# design.net
KiCad netlist of a schematic drawn in Altium Designer
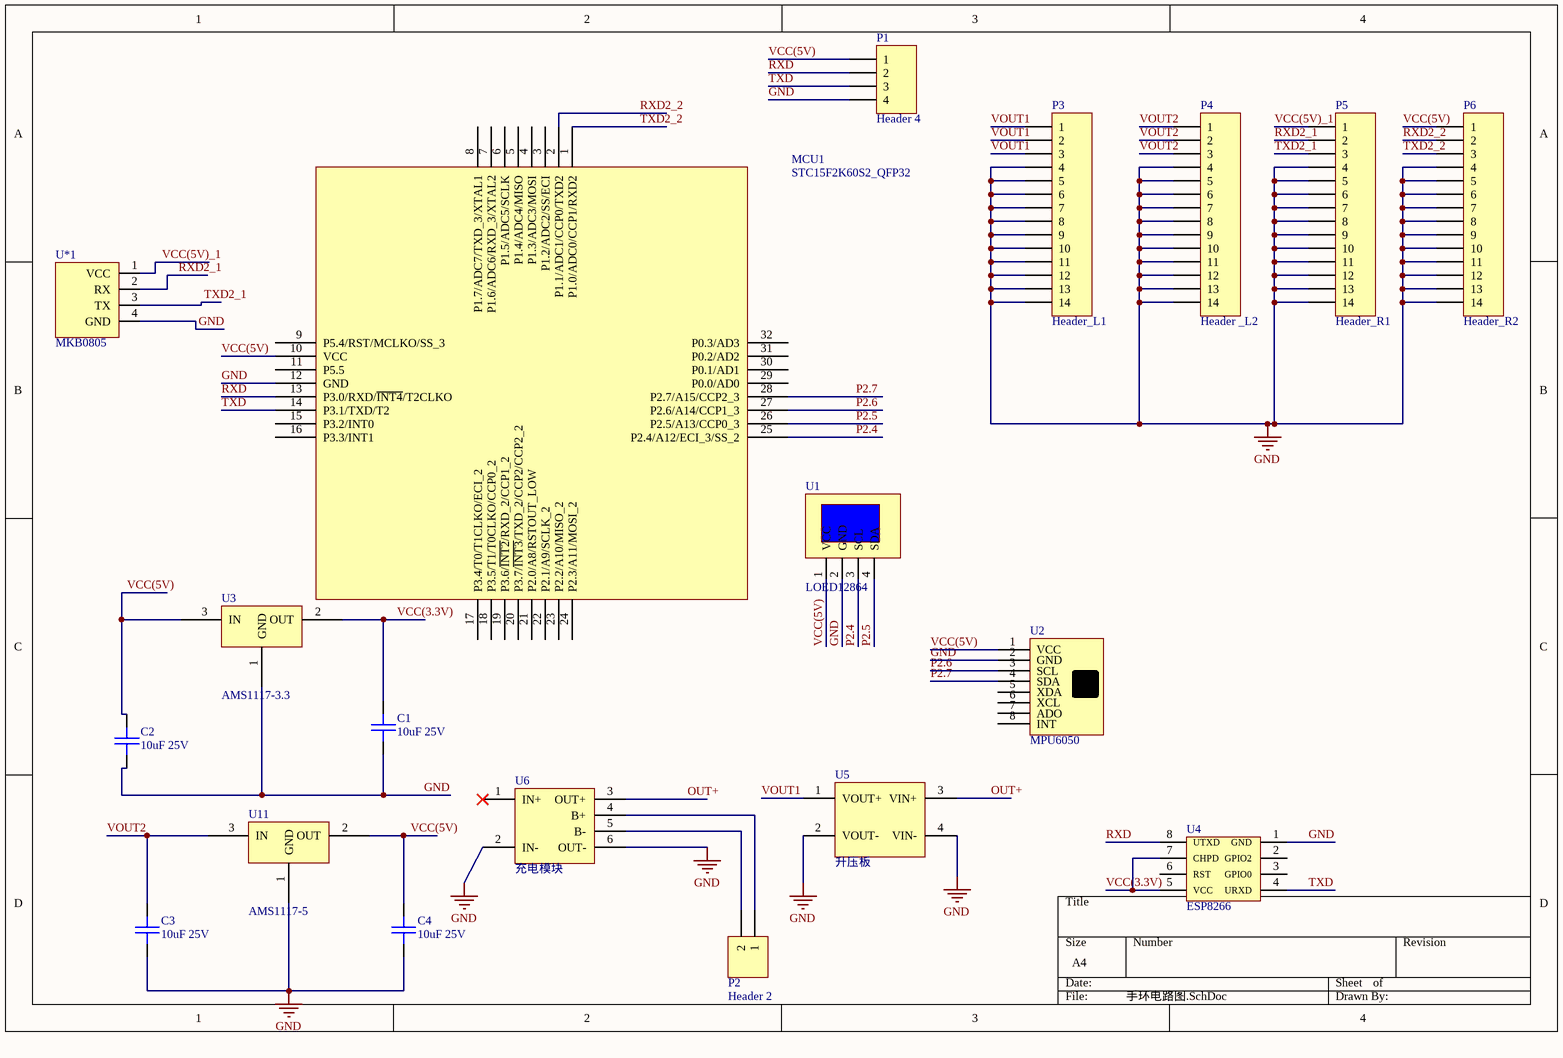
[diagram p0: 手环电路图.SchDoc]

(export (version "E")
  (design (tool "Eeschema 10.0.6"))
  (components
    (comp (ref "C1")
      (value "10uF 25V")
      (footprint "SMT_C_0805")
      (description "Surface mount capacitor 0805")
      (libsource (lib "NODEMCU_DEVKIT_V1.0") (part "SMT_C_0805"))
    )
    (comp (ref "C2")
      (value "10uF 25V")
      (footprint "SMT_C_0805")
      (description "Surface mount capacitor 0805")
      (libsource (lib "NODEMCU_DEVKIT_V1.0") (part "SMT_C_0805"))
    )
    (comp (ref "C3")
      (value "10uF 25V")
      (footprint "SMT_C_0805")
      (description "Surface mount capacitor 0805")
      (libsource (lib "NODEMCU_DEVKIT_V1.0") (part "SMT_C_0805"))
    )
    (comp (ref "C4")
      (value "10uF 25V")
      (footprint "SMT_C_0805")
      (description "Surface mount capacitor 0805")
      (libsource (lib "NODEMCU_DEVKIT_V1.0") (part "SMT_C_0805"))
    )
    (comp (ref "MCU1")
      (value "STC15F2K60S2_QFP32")
      (footprint "LQFP32")
      (libsource (lib "stcmcu_altium_lib") (part "STC15F2K60S2_QFP32"))
    )
    (comp (ref "P1")
      (value "Header 4")
      (footprint "HDR1X4")
      (description "Header, 4-Pin")
      (fields (field (name "PUBLISHER") "Altium Limited"))
      (libsource (lib "Miscellaneous Connectors") (part "Header 4"))
    )
    (comp (ref "P2")
      (value "Header 2")
      (footprint "HDR1X2")
      (description "Header, 2-Pin")
      (fields (field (name "PUBLISHER") "Altium Limited"))
      (libsource (lib "Miscellaneous Connectors") (part "Header 2"))
    )
    (comp (ref "P3")
      (value "Header_L1")
      (footprint "HDR1X14")
      (description "Header, 14-Pin")
      (fields (field (name "PUBLISHER") "Altium Limited"))
      (libsource (lib "Miscellaneous Connectors") (part "Header 14"))
    )
    (comp (ref "P4")
      (value "Header _L2")
      (footprint "HDR1X14")
      (description "Header, 14-Pin")
      (fields (field (name "PUBLISHER") "Altium Limited"))
      (libsource (lib "Miscellaneous Connectors") (part "Header 14"))
    )
    (comp (ref "P5")
      (value "Header_R1")
      (footprint "HDR1X14")
      (description "Header, 14-Pin")
      (fields (field (name "PUBLISHER") "Altium Limited"))
      (libsource (lib "Miscellaneous Connectors") (part "Header 14"))
    )
    (comp (ref "P6")
      (value "Header_R2")
      (footprint "HDR1X14")
      (description "Header, 14-Pin")
      (fields (field (name "PUBLISHER") "Altium Limited"))
      (libsource (lib "Miscellaneous Connectors") (part "Header 14"))
    )
    (comp (ref "U*1") (value "MKB0805") (footprint "MKB0805") (libsource (lib "oldman") (part "MKB0805")))
    (comp (ref "U1")
      (value "LOED12864")
      (footprint "OLED12864")
      (libsource (lib "oldman") (part "LOED12864"))
    )
    (comp (ref "U2") (value "MPU6050") (footprint "MPU6050") (libsource (lib "oldman") (part "MPU6050")))
    (comp (ref "U3") (value "AMS1117-3.3") (footprint "AMS1117") (libsource (lib "NFC") (part "AMS1117-3.3")))
    (comp (ref "U4") (value "ESP8266") (footprint "ESP8266") (libsource (lib "oldman") (part "ESP8266")))
    (comp (ref "U5") (value "升压板") (footprint "MT3608") (libsource (lib "oldman") (part "MT3608")))
    (comp (ref "U6") (value "充电模块") (footprint "HW373") (libsource (lib "oldman") (part "HW373")))
    (comp (ref "U11") (value "AMS1117-5") (footprint "AMS1117") (libsource (lib "NFC") (part "AMS1117-3.3")))
  )
  (nets
    (net (code "1") (name "/OUT+") (class "Default")
      (node (ref "U5") (pin "3") (pinfunction "VIN+_3") (pintype "passive"))
      (node (ref "U6") (pin "3") (pinfunction "OUT+_3") (pintype "passive"))
    )
    (net (code "2") (name "/P2.4") (class "Default")
      (node (ref "MCU1") (pin "25") (pinfunction "P2.4/A12/ECI_3/SS_2_25") (pintype "passive"))
      (node (ref "U1") (pin "3") (pinfunction "SCL_3") (pintype "passive"))
    )
    (net (code "3") (name "/P2.5") (class "Default")
      (node (ref "MCU1") (pin "26") (pinfunction "P2.5/A13/CCP0_3_26") (pintype "passive"))
      (node (ref "U1") (pin "4") (pinfunction "SDA_4") (pintype "passive"))
    )
    (net (code "4") (name "/P2.6") (class "Default")
      (node (ref "MCU1") (pin "27") (pinfunction "P2.6/A14/CCP1_3_27") (pintype "passive"))
      (node (ref "U2") (pin "3") (pinfunction "SCL_3") (pintype "passive"))
    )
    (net (code "5") (name "/P2.7") (class "Default")
      (node (ref "MCU1") (pin "28") (pinfunction "P2.7/A15/CCP2_3_28") (pintype "passive"))
      (node (ref "U2") (pin "4") (pinfunction "SDA_4") (pintype "passive"))
    )
    (net (code "6") (name "/RXD") (class "Default")
      (node (ref "MCU1") (pin "13") (pinfunction "P3.0/RXD/~{INT4}/T2CLKO_13") (pintype "passive"))
      (node (ref "P1") (pin "2") (pinfunction "2_2") (pintype "passive"))
      (node (ref "U4") (pin "8") (pinfunction "UTXD_8") (pintype "passive"))
    )
    (net (code "7") (name "/RXD2_1") (class "Default")
      (node (ref "P5") (pin "2") (pinfunction "2_2") (pintype "passive"))
      (node (ref "U*1") (pin "2") (pinfunction "RX_2") (pintype "passive"))
    )
    (net (code "8") (name "/RXD2_2") (class "Default")
      (node (ref "MCU1") (pin "2") (pinfunction "P1.1/ADC1/CCP0/TXD2_2") (pintype "passive"))
      (node (ref "P6") (pin "2") (pinfunction "2_2") (pintype "passive"))
    )
    (net (code "9") (name "/TXD") (class "Default")
      (node (ref "MCU1") (pin "14") (pinfunction "P3.1/TXD/T2_14") (pintype "passive"))
      (node (ref "P1") (pin "3") (pinfunction "3_3") (pintype "passive"))
      (node (ref "U4") (pin "4") (pinfunction "URXD_4") (pintype "passive"))
    )
    (net (code "10") (name "/TXD2_1") (class "Default")
      (node (ref "P5") (pin "3") (pinfunction "3_3") (pintype "passive"))
      (node (ref "U*1") (pin "3") (pinfunction "TX_3") (pintype "passive"))
    )
    (net (code "11") (name "/TXD2_2") (class "Default")
      (node (ref "MCU1") (pin "1") (pinfunction "P1.0/ADC0/CCP1/RXD2_1") (pintype "passive"))
      (node (ref "P6") (pin "3") (pinfunction "3_3") (pintype "passive"))
    )
    (net (code "12") (name "/VCC(3.3V)") (class "Default")
      (node (ref "C1") (pin "1") (pinfunction "1_1") (pintype "passive"))
      (node (ref "U3") (pin "2") (pinfunction "OUT_2") (pintype "passive"))
      (node (ref "U4") (pin "5") (pinfunction "VCC_5") (pintype "power_in"))
      (node (ref "U4") (pin "7") (pinfunction "CHPD_7") (pintype "passive"))
    )
    (net (code "13") (name "/VCC(5V)") (class "Default")
      (node (ref "C2") (pin "1") (pinfunction "1_1") (pintype "passive"))
      (node (ref "C4") (pin "1") (pinfunction "1_1") (pintype "passive"))
      (node (ref "MCU1") (pin "10") (pinfunction "VCC_10") (pintype "passive"))
      (node (ref "P1") (pin "1") (pinfunction "1_1") (pintype "passive"))
      (node (ref "P6") (pin "1") (pinfunction "1_1") (pintype "passive"))
      (node (ref "U1") (pin "1") (pinfunction "VCC_1") (pintype "passive"))
      (node (ref "U11") (pin "2") (pinfunction "OUT_2") (pintype "passive"))
      (node (ref "U2") (pin "1") (pinfunction "VCC_1") (pintype "passive"))
      (node (ref "U3") (pin "3") (pinfunction "IN_3") (pintype "passive"))
    )
    (net (code "14") (name "/VCC(5V)_1") (class "Default")
      (node (ref "P5") (pin "1") (pinfunction "1_1") (pintype "passive"))
      (node (ref "U*1") (pin "1") (pinfunction "VCC_1") (pintype "passive"))
    )
    (net (code "15") (name "/VOUT1") (class "Default")
      (node (ref "P3") (pin "1") (pinfunction "1_1") (pintype "passive"))
      (node (ref "P3") (pin "2") (pinfunction "2_2") (pintype "passive"))
      (node (ref "P3") (pin "3") (pinfunction "3_3") (pintype "passive"))
      (node (ref "U5") (pin "1") (pinfunction "VOUT+_1") (pintype "passive"))
    )
    (net (code "16") (name "/VOUT2") (class "Default")
      (node (ref "C3") (pin "1") (pinfunction "1_1") (pintype "passive"))
      (node (ref "P4") (pin "1") (pinfunction "1_1") (pintype "passive"))
      (node (ref "P4") (pin "2") (pinfunction "2_2") (pintype "passive"))
      (node (ref "P4") (pin "3") (pinfunction "3_3") (pintype "passive"))
      (node (ref "U11") (pin "3") (pinfunction "IN_3") (pintype "passive"))
    )
    (net (code "17") (name "GND") (class "Default")
      (node (ref "C1") (pin "2") (pinfunction "2_2") (pintype "passive"))
      (node (ref "C2") (pin "2") (pinfunction "2_2") (pintype "passive"))
      (node (ref "C3") (pin "2") (pinfunction "2_2") (pintype "passive"))
      (node (ref "C4") (pin "2") (pinfunction "2_2") (pintype "passive"))
      (node (ref "MCU1") (pin "12") (pinfunction "GND_12") (pintype "passive"))
      (node (ref "P1") (pin "4") (pinfunction "4_4") (pintype "passive"))
      (node (ref "P3") (pin "10") (pinfunction "10_10") (pintype "passive"))
      (node (ref "P3") (pin "11") (pinfunction "11_11") (pintype "passive"))
      (node (ref "P3") (pin "12") (pinfunction "12_12") (pintype "passive"))
      (node (ref "P3") (pin "13") (pinfunction "13_13") (pintype "passive"))
      (node (ref "P3") (pin "14") (pinfunction "14_14") (pintype "passive"))
      (node (ref "P3") (pin "4") (pinfunction "4_4") (pintype "passive"))
      (node (ref "P3") (pin "5") (pinfunction "5_5") (pintype "passive"))
      (node (ref "P3") (pin "6") (pinfunction "6_6") (pintype "passive"))
      (node (ref "P3") (pin "7") (pinfunction "7_7") (pintype "passive"))
      (node (ref "P3") (pin "8") (pinfunction "8_8") (pintype "passive"))
      (node (ref "P3") (pin "9") (pinfunction "9_9") (pintype "passive"))
      (node (ref "P4") (pin "10") (pinfunction "10_10") (pintype "passive"))
      (node (ref "P4") (pin "11") (pinfunction "11_11") (pintype "passive"))
      (node (ref "P4") (pin "12") (pinfunction "12_12") (pintype "passive"))
      (node (ref "P4") (pin "13") (pinfunction "13_13") (pintype "passive"))
      (node (ref "P4") (pin "14") (pinfunction "14_14") (pintype "passive"))
      (node (ref "P4") (pin "4") (pinfunction "4_4") (pintype "passive"))
      (node (ref "P4") (pin "5") (pinfunction "5_5") (pintype "passive"))
      (node (ref "P4") (pin "6") (pinfunction "6_6") (pintype "passive"))
      (node (ref "P4") (pin "7") (pinfunction "7_7") (pintype "passive"))
      (node (ref "P4") (pin "8") (pinfunction "8_8") (pintype "passive"))
      (node (ref "P4") (pin "9") (pinfunction "9_9") (pintype "passive"))
      (node (ref "P5") (pin "10") (pinfunction "10_10") (pintype "passive"))
      (node (ref "P5") (pin "11") (pinfunction "11_11") (pintype "passive"))
      (node (ref "P5") (pin "12") (pinfunction "12_12") (pintype "passive"))
      (node (ref "P5") (pin "13") (pinfunction "13_13") (pintype "passive"))
      (node (ref "P5") (pin "14") (pinfunction "14_14") (pintype "passive"))
      (node (ref "P5") (pin "4") (pinfunction "4_4") (pintype "passive"))
      (node (ref "P5") (pin "5") (pinfunction "5_5") (pintype "passive"))
      (node (ref "P5") (pin "6") (pinfunction "6_6") (pintype "passive"))
      (node (ref "P5") (pin "7") (pinfunction "7_7") (pintype "passive"))
      (node (ref "P5") (pin "8") (pinfunction "8_8") (pintype "passive"))
      (node (ref "P5") (pin "9") (pinfunction "9_9") (pintype "passive"))
      (node (ref "P6") (pin "10") (pinfunction "10_10") (pintype "passive"))
      (node (ref "P6") (pin "11") (pinfunction "11_11") (pintype "passive"))
      (node (ref "P6") (pin "12") (pinfunction "12_12") (pintype "passive"))
      (node (ref "P6") (pin "13") (pinfunction "13_13") (pintype "passive"))
      (node (ref "P6") (pin "14") (pinfunction "14_14") (pintype "passive"))
      (node (ref "P6") (pin "4") (pinfunction "4_4") (pintype "passive"))
      (node (ref "P6") (pin "5") (pinfunction "5_5") (pintype "passive"))
      (node (ref "P6") (pin "6") (pinfunction "6_6") (pintype "passive"))
      (node (ref "P6") (pin "7") (pinfunction "7_7") (pintype "passive"))
      (node (ref "P6") (pin "8") (pinfunction "8_8") (pintype "passive"))
      (node (ref "P6") (pin "9") (pinfunction "9_9") (pintype "passive"))
      (node (ref "U*1") (pin "4") (pinfunction "GND_4") (pintype "passive"))
      (node (ref "U1") (pin "2") (pinfunction "GND_2") (pintype "passive"))
      (node (ref "U11") (pin "1") (pinfunction "GND_1") (pintype "passive"))
      (node (ref "U2") (pin "2") (pinfunction "GND_2") (pintype "passive"))
      (node (ref "U3") (pin "1") (pinfunction "GND_1") (pintype "passive"))
      (node (ref "U4") (pin "1") (pinfunction "GND_1") (pintype "passive"))
      (node (ref "U5") (pin "2") (pinfunction "VOUT-_2") (pintype "passive"))
      (node (ref "U5") (pin "4") (pinfunction "VIN-_4") (pintype "passive"))
      (node (ref "U6") (pin "2") (pinfunction "IN-_2") (pintype "passive"))
      (node (ref "U6") (pin "6") (pinfunction "OUT-_6") (pintype "passive"))
    )
    (net (code "18") (name "Net-(U6-B+)") (class "Default")
      (node (ref "P2") (pin "1") (pinfunction "1_1") (pintype "passive"))
      (node (ref "U6") (pin "4") (pinfunction "B+_4") (pintype "passive"))
    )
    (net (code "19") (name "Net-(U6-B-)") (class "Default")
      (node (ref "P2") (pin "2") (pinfunction "2_2") (pintype "passive"))
      (node (ref "U6") (pin "5") (pinfunction "B-_5") (pintype "passive"))
    )
    (net (code "20") (name "unconnected-(MCU1-P0.0{slash}AD0-Pad29)") (class "Default")
      (node (ref "MCU1") (pin "29") (pinfunction "P0.0/AD0_29") (pintype "passive"))
    )
    (net (code "21") (name "unconnected-(MCU1-P0.1{slash}AD1-Pad30)") (class "Default")
      (node (ref "MCU1") (pin "30") (pinfunction "P0.1/AD1_30") (pintype "passive"))
    )
    (net (code "22") (name "unconnected-(MCU1-P0.2{slash}AD2-Pad31)") (class "Default")
      (node (ref "MCU1") (pin "31") (pinfunction "P0.2/AD2_31") (pintype "passive"))
    )
    (net (code "23") (name "unconnected-(MCU1-P0.3{slash}AD3-Pad32)") (class "Default")
      (node (ref "MCU1") (pin "32") (pinfunction "P0.3/AD3_32") (pintype "passive"))
    )
    (net (code "24") (name "unconnected-(MCU1-P1.2{slash}ADC2{slash}SS{slash}ECI-Pad3)") (class "Default")
      (node (ref "MCU1") (pin "3") (pinfunction "P1.2/ADC2/SS/ECI_3") (pintype "passive"))
    )
    (net (code "25") (name "unconnected-(MCU1-P1.3{slash}ADC3{slash}MOSI-Pad4)") (class "Default")
      (node (ref "MCU1") (pin "4") (pinfunction "P1.3/ADC3/MOSI_4") (pintype "passive"))
    )
    (net (code "26") (name "unconnected-(MCU1-P1.4{slash}ADC4{slash}MISO-Pad5)") (class "Default")
      (node (ref "MCU1") (pin "5") (pinfunction "P1.4/ADC4/MISO_5") (pintype "passive"))
    )
    (net (code "27") (name "unconnected-(MCU1-P1.5{slash}ADC5{slash}SCLK-Pad6)") (class "Default")
      (node (ref "MCU1") (pin "6") (pinfunction "P1.5/ADC5/SCLK_6") (pintype "passive"))
    )
    (net (code "28") (name "unconnected-(MCU1-P1.6{slash}ADC6{slash}RXD_3{slash}XTAL2-Pad7)") (class "Default")
      (node (ref "MCU1") (pin "7") (pinfunction "P1.6/ADC6/RXD_3/XTAL2_7") (pintype "passive"))
    )
    (net (code "29") (name "unconnected-(MCU1-P1.7{slash}ADC7{slash}TXD_3{slash}XTAL1-Pad8)") (class "Default")
      (node (ref "MCU1") (pin "8") (pinfunction "P1.7/ADC7/TXD_3/XTAL1_8") (pintype "passive"))
    )
    (net (code "30") (name "unconnected-(MCU1-P2.0{slash}A8{slash}RSTOUT_LOW-Pad21)") (class "Default")
      (node (ref "MCU1") (pin "21") (pinfunction "P2.0/A8/RSTOUT_LOW_21") (pintype "passive"))
    )
    (net (code "31") (name "unconnected-(MCU1-P2.1{slash}A9{slash}SCLK_2-Pad22)") (class "Default")
      (node (ref "MCU1") (pin "22") (pinfunction "P2.1/A9/SCLK_2_22") (pintype "passive"))
    )
    (net (code "32") (name "unconnected-(MCU1-P2.2{slash}A10{slash}MISO_2-Pad23)") (class "Default")
      (node (ref "MCU1") (pin "23") (pinfunction "P2.2/A10/MISO_2_23") (pintype "passive"))
    )
    (net (code "33") (name "unconnected-(MCU1-P2.3{slash}A11{slash}MOSI_2-Pad24)") (class "Default")
      (node (ref "MCU1") (pin "24") (pinfunction "P2.3/A11/MOSI_2_24") (pintype "passive"))
    )
    (net (code "34") (name "unconnected-(MCU1-P3.2{slash}INT0-Pad15)") (class "Default")
      (node (ref "MCU1") (pin "15") (pinfunction "P3.2/INT0_15") (pintype "passive"))
    )
    (net (code "35") (name "unconnected-(MCU1-P3.3{slash}INT1-Pad16)") (class "Default")
      (node (ref "MCU1") (pin "16") (pinfunction "P3.3/INT1_16") (pintype "passive"))
    )
    (net (code "36") (name "unconnected-(MCU1-P3.4{slash}T0{slash}T1CLKO{slash}ECI_2-Pad17)") (class "Default")
      (node (ref "MCU1") (pin "17") (pinfunction "P3.4/T0/T1CLKO/ECI_2_17") (pintype "passive"))
    )
    (net (code "37") (name "unconnected-(MCU1-P3.5{slash}T1{slash}T0CLKO{slash}CCP0_2-Pad18)") (class "Default")
      (node (ref "MCU1") (pin "18") (pinfunction "P3.5/T1/T0CLKO/CCP0_2_18") (pintype "passive"))
    )
    (net (code "38") (name "unconnected-(MCU1-P3.6{slash}~{INT2}{slash}RXD_2{slash}CCP1_2-Pad19)") (class "Default")
      (node (ref "MCU1") (pin "19") (pinfunction "P3.6/~{INT2}/RXD_2/CCP1_2_19") (pintype "passive"))
    )
    (net (code "39") (name "unconnected-(MCU1-P3.7{slash}~{INT3}{slash}TXD_2{slash}CCP2{slash}CCP2_2-Pad20)") (class "Default")
      (node (ref "MCU1") (pin "20") (pinfunction "P3.7/~{INT3}/TXD_2/CCP2/CCP2_2_20") (pintype "passive"))
    )
    (net (code "40") (name "unconnected-(MCU1-P5.4{slash}RST{slash}MCLKO{slash}SS_3-Pad9)") (class "Default")
      (node (ref "MCU1") (pin "9") (pinfunction "P5.4/RST/MCLKO/SS_3_9") (pintype "passive"))
    )
    (net (code "41") (name "unconnected-(MCU1-P5.5-Pad11)") (class "Default")
      (node (ref "MCU1") (pin "11") (pinfunction "P5.5_11") (pintype "passive"))
    )
    (net (code "42") (name "unconnected-(U2-ADO-Pad7)") (class "Default")
      (node (ref "U2") (pin "7") (pinfunction "ADO_7") (pintype "passive"))
    )
    (net (code "43") (name "unconnected-(U2-INT-Pad8)") (class "Default")
      (node (ref "U2") (pin "8") (pinfunction "INT_8") (pintype "passive"))
    )
    (net (code "44") (name "unconnected-(U2-XCL-Pad6)") (class "Default")
      (node (ref "U2") (pin "6") (pinfunction "XCL_6") (pintype "passive"))
    )
    (net (code "45") (name "unconnected-(U2-XDA-Pad5)") (class "Default")
      (node (ref "U2") (pin "5") (pinfunction "XDA_5") (pintype "passive"))
    )
    (net (code "46") (name "unconnected-(U4-GPIO0-Pad3)") (class "Default")
      (node (ref "U4") (pin "3") (pinfunction "GPIO0_3") (pintype "passive"))
    )
    (net (code "47") (name "unconnected-(U4-GPIO2-Pad2)") (class "Default")
      (node (ref "U4") (pin "2") (pinfunction "GPIO2_2") (pintype "passive"))
    )
    (net (code "48") (name "unconnected-(U4-RST-Pad6)") (class "Default")
      (node (ref "U4") (pin "6") (pinfunction "RST_6") (pintype "passive"))
    )
    (net (code "49") (name "unconnected-(U6-IN+-Pad1)") (class "Default")
      (node (ref "U6") (pin "1") (pinfunction "IN+_1") (pintype "passive+no_connect"))
    )
  )
)
